# port.net
KiCad netlist of a schematic drawn in Altium Designer
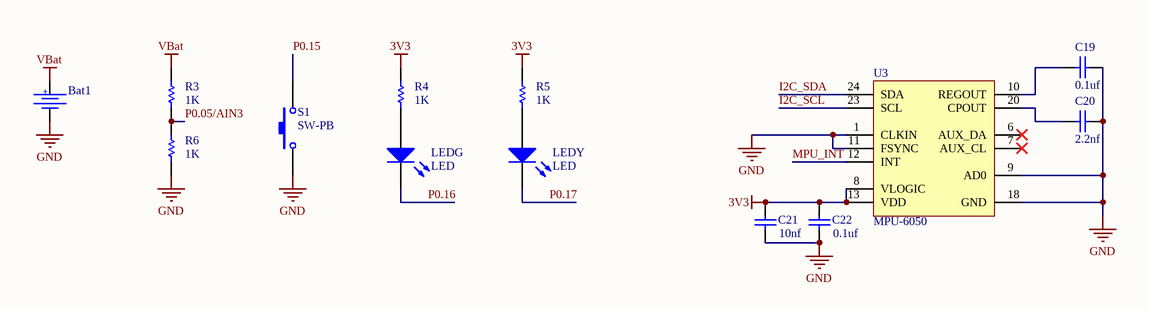
[diagram p0: port.SchDoc]

(export (version "E")
  (design (tool "Eeschema 10.0.6"))
  (components
    (comp (ref "Bat1")
      (value "Bat Holder CR2032")
      (footprint "HDR1X2")
      (description "Bat Holder CR2032 SMD")
      (fields
        (field (name "MANUFACTURER") "Comfortable")
        (field (name "MANUFACTURER PART NUMBER") "BC-2001")
        (field (name "PUBLISHER") "Nordic Semiconductor")
      )
      (libsource (lib "Mylibrary") (part "Battery"))
    )
    (comp (ref "C19")
      (value "0.1uf")
      (footprint "C0603")
      (description "Capacitor (Semiconductor SIM Model)")
      (fields (field (name "Comment") "Cap Semi") (field (name "PUBLISHER") "Altium Limited"))
      (libsource (lib "Mylibrary") (part "Cap Semi"))
    )
    (comp (ref "C20")
      (value "2.2nf")
      (footprint "C0603")
      (description "Capacitor (Semiconductor SIM Model)")
      (fields (field (name "Comment") "Cap Semi") (field (name "PUBLISHER") "Altium Limited"))
      (libsource (lib "Mylibrary") (part "Cap Semi"))
    )
    (comp (ref "C21")
      (value "10nf")
      (footprint "C0603")
      (description "Capacitor (Semiconductor SIM Model)")
      (fields (field (name "Comment") "Cap Semi") (field (name "PUBLISHER") "Altium Limited"))
      (libsource (lib "Mylibrary") (part "Cap Semi"))
    )
    (comp (ref "C22")
      (value "0.1uf")
      (footprint "C0603")
      (description "Capacitor (Semiconductor SIM Model)")
      (fields (field (name "Comment") "Cap Semi") (field (name "PUBLISHER") "Altium Limited"))
      (libsource (lib "Mylibrary") (part "Cap Semi"))
    )
    (comp (ref "LEDG")
      (value "LED")
      (footprint "0603")
      (description "Typical INFRARED GaAs LED")
      (fields (field (name "PUBLISHER") "Altium Limited"))
      (libsource (lib "Mylibrary") (part "LED"))
    )
    (comp (ref "LEDY")
      (value "LED")
      (footprint "0603")
      (description "Typical INFRARED GaAs LED")
      (fields (field (name "PUBLISHER") "Altium Limited"))
      (libsource (lib "Mylibrary") (part "LED"))
    )
    (comp (ref "R3")
      (value "1K")
      (footprint "R0603-M")
      (description "Resistor")
      (fields (field (name "Comment") "Resistors SMD"))
      (libsource (lib "Mylibrary") (part "Resistors SMD"))
    )
    (comp (ref "R4")
      (value "1K")
      (footprint "R0603-M")
      (description "Resistor")
      (fields (field (name "Comment") "Resistors SMD"))
      (libsource (lib "Mylibrary") (part "Resistors SMD"))
    )
    (comp (ref "R5")
      (value "1K")
      (footprint "R0603-M")
      (description "Resistor")
      (fields (field (name "Comment") "Resistors SMD"))
      (libsource (lib "Mylibrary") (part "Resistors SMD"))
    )
    (comp (ref "R6")
      (value "1K")
      (footprint "R0603-M")
      (description "Resistor")
      (fields (field (name "Comment") "Resistors SMD"))
      (libsource (lib "Mylibrary") (part "Resistors SMD"))
    )
    (comp (ref "S1")
      (value "SW-PB")
      (footprint "SWITCH_SMD_4x3_DHT-1185")
      (description "Switch")
      (fields (field (name "PUBLISHER") "Altium Limited"))
      (libsource (lib "Mylibrary") (part "SW-PB"))
    )
    (comp (ref "U3")
      (value "MPU-6050")
      (footprint "MPU-6050")
      (libsource (lib "Mylibrary") (part "MPU-6050"))
    )
  )
  (nets
    (net (code "1") (name "/I2C_SCL") (class "Default")
      (node (ref "U3") (pin "23") (pinfunction "SCL_23") (pintype "passive"))
    )
    (net (code "2") (name "/I2C_SDA") (class "Default")
      (node (ref "U3") (pin "24") (pinfunction "SDA_24") (pintype "passive"))
    )
    (net (code "3") (name "/MPU_INT") (class "Default")
      (node (ref "U3") (pin "12") (pinfunction "INT_12") (pintype "passive"))
    )
    (net (code "4") (name "/P0.05{slash}AIN3") (class "Default")
      (node (ref "R3") (pin "1") (pinfunction "1_1") (pintype "passive"))
      (node (ref "R6") (pin "2") (pinfunction "2_2") (pintype "passive"))
    )
    (net (code "5") (name "/P0.15") (class "Default")
      (node (ref "S1") (pin "2") (pinfunction "2_2") (pintype "passive"))
    )
    (net (code "6") (name "/P0.16") (class "Default")
      (node (ref "LEDG") (pin "2") (pinfunction "K_2") (pintype "passive"))
    )
    (net (code "7") (name "/P0.17") (class "Default")
      (node (ref "LEDY") (pin "2") (pinfunction "K_2") (pintype "passive"))
    )
    (net (code "8") (name "3V3") (class "Default")
      (node (ref "C21") (pin "2") (pinfunction "2_2") (pintype "passive"))
      (node (ref "C22") (pin "2") (pinfunction "2_2") (pintype "passive"))
      (node (ref "R4") (pin "2") (pinfunction "2_2") (pintype "passive"))
      (node (ref "R5") (pin "2") (pinfunction "2_2") (pintype "passive"))
      (node (ref "U3") (pin "13") (pinfunction "VDD_13") (pintype "passive"))
      (node (ref "U3") (pin "8") (pinfunction "VLOGIC_8") (pintype "passive"))
    )
    (net (code "9") (name "GND") (class "Default")
      (node (ref "Bat1") (pin "2") (pintype "passive"))
      (node (ref "C19") (pin "1") (pinfunction "1_1") (pintype "passive"))
      (node (ref "C20") (pin "1") (pinfunction "1_1") (pintype "passive"))
      (node (ref "C21") (pin "1") (pinfunction "1_1") (pintype "passive"))
      (node (ref "C22") (pin "1") (pinfunction "1_1") (pintype "passive"))
      (node (ref "R6") (pin "1") (pinfunction "1_1") (pintype "passive"))
      (node (ref "S1") (pin "1") (pinfunction "1_1") (pintype "passive"))
      (node (ref "U3") (pin "1") (pinfunction "CLKIN_1") (pintype "passive"))
      (node (ref "U3") (pin "11") (pinfunction "FSYNC_11") (pintype "passive"))
      (node (ref "U3") (pin "18") (pinfunction "GND_18") (pintype "passive"))
      (node (ref "U3") (pin "9") (pinfunction "AD0_9") (pintype "passive"))
    )
    (net (code "10") (name "Net-(LEDG-A)") (class "Default")
      (node (ref "LEDG") (pin "1") (pinfunction "A_1") (pintype "passive"))
      (node (ref "R4") (pin "1") (pinfunction "1_1") (pintype "passive"))
    )
    (net (code "11") (name "Net-(LEDY-A)") (class "Default")
      (node (ref "LEDY") (pin "1") (pinfunction "A_1") (pintype "passive"))
      (node (ref "R5") (pin "1") (pinfunction "1_1") (pintype "passive"))
    )
    (net (code "12") (name "Net-(U3-CPOUT)") (class "Default")
      (node (ref "C20") (pin "2") (pinfunction "2_2") (pintype "passive"))
      (node (ref "U3") (pin "20") (pinfunction "CPOUT_20") (pintype "passive"))
    )
    (net (code "13") (name "Net-(U3-REGOUT)") (class "Default")
      (node (ref "C19") (pin "2") (pinfunction "2_2") (pintype "passive"))
      (node (ref "U3") (pin "10") (pinfunction "REGOUT_10") (pintype "passive"))
    )
    (net (code "14") (name "VBat") (class "Default")
      (node (ref "Bat1") (pin "1") (pintype "passive"))
      (node (ref "R3") (pin "2") (pinfunction "2_2") (pintype "passive"))
    )
    (net (code "15") (name "unconnected-(U3-AUX_CL-Pad7)") (class "Default")
      (node (ref "U3") (pin "7") (pinfunction "AUX_CL_7") (pintype "passive+no_connect"))
    )
    (net (code "16") (name "unconnected-(U3-AUX_DA-Pad6)") (class "Default")
      (node (ref "U3") (pin "6") (pinfunction "AUX_DA_6") (pintype "passive+no_connect"))
    )
  )
)
